# Switching_Circuit.net
KiCad netlist of a schematic drawn in EAGLE
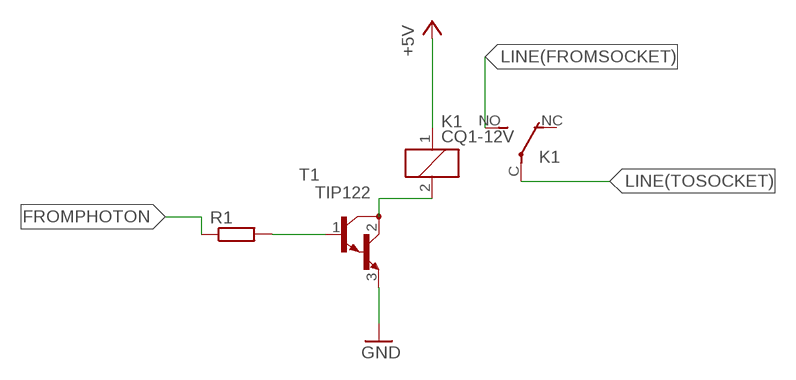
[diagram p0: schematic, sheet 1]

(export (version "E")
  (design (tool "Eeschema 10.0.6"))
  (components
    (comp (ref "K1")
      (value "CQ1-12V")
      (footprint "eagle-import:CQ1")
      (libsource (lib "eagle-import") (part "CQ1-12V"))
    )
    (comp (ref "R1")
      (value "R-EU_0204/7")
      (footprint "eagle-import:0204_7")
      (libsource (lib "eagle-import") (part "R-EU_0204/7"))
    )
    (comp (ref "T1")
      (value "TIP122")
      (footprint "eagle-import:TO220")
      (libsource (lib "eagle-import") (part "TIP122"))
    )
  )
  (nets
    (net (code "1") (name "+5V") (class "Default")
      (node (ref "K1") (pin "1") (pinfunction "1_1") (pintype "passive"))
    )
    (net (code "2") (name "FROMPHOTON") (class "Default")
      (node (ref "R1") (pin "1") (pinfunction "1_1") (pintype "passive"))
    )
    (net (code "3") (name "GND") (class "Default")
      (node (ref "T1") (pin "3") (pinfunction "E_3") (pintype "passive"))
    )
    (net (code "4") (name "LINE(FROMSOCKET)") (class "Default")
      (node (ref "K1") (pin "NO") (pinfunction "S_NO") (pintype "passive"))
    )
    (net (code "5") (name "LINE(TOSOCKET)") (class "Default")
      (node (ref "K1") (pin "C") (pinfunction "P_C") (pintype "passive"))
    )
    (net (code "6") (name "Net-(T1-B)") (class "Default")
      (node (ref "R1") (pin "2") (pinfunction "2_2") (pintype "passive"))
      (node (ref "T1") (pin "1") (pinfunction "B_1") (pintype "passive"))
    )
    (net (code "7") (name "Net-(T1-C)") (class "Default")
      (node (ref "K1") (pin "2") (pinfunction "2_2") (pintype "passive"))
      (node (ref "T1") (pin "2") (pinfunction "C_2") (pintype "passive"))
    )
    (net (code "8") (name "unconnected-(K1B-O-PadNC)") (class "Default")
      (node (ref "K1") (pin "NC") (pinfunction "O_NC") (pintype "passive"))
    )
  )
)
